# touch_7.net
KiCad netlist of a schematic drawn in EAGLE
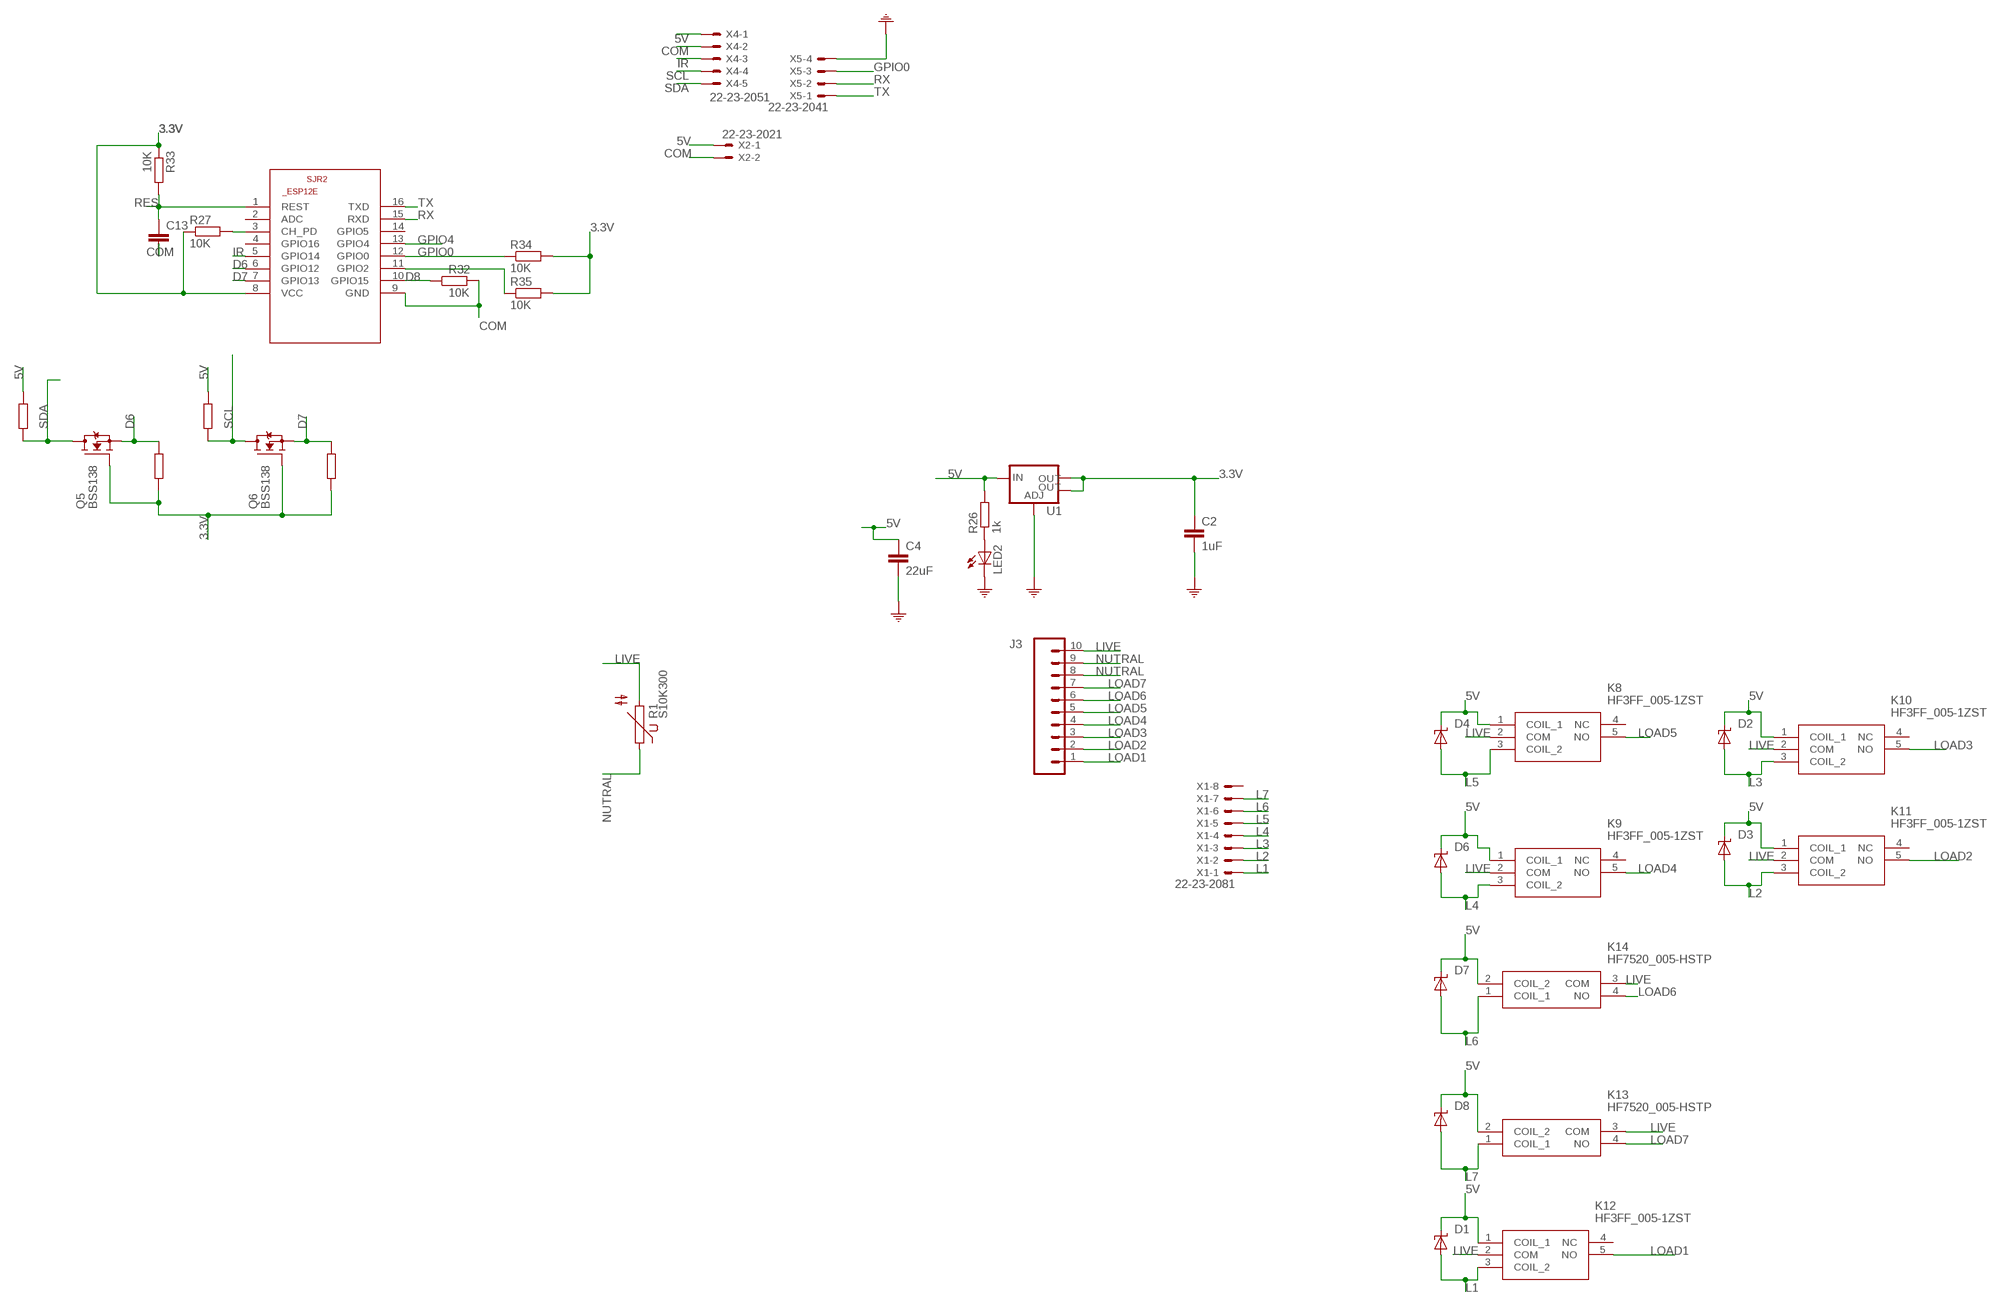
[diagram p0: schematic, sheet 1]

(export (version "E")
  (design (tool "Eeschema 10.0.6"))
  (components
    (comp (ref "C2")
      (value "1uF")
      (footprint "eagle-import:C1206")
      (libsource (lib "eagle-import") (part "C-EUC1206"))
    )
    (comp (ref "C4")
      (value "22uF")
      (footprint "eagle-import:C1206")
      (libsource (lib "eagle-import") (part "C-EUC1206"))
    )
    (comp (ref "C13")
      (value "C-EUC0805")
      (footprint "eagle-import:C0805")
      (libsource (lib "eagle-import") (part "C-EUC0805"))
    )
    (comp (ref "D1")
      (value "SUPPRESSOR-SMBJ")
      (footprint "eagle-import:SMBJ")
      (libsource (lib "eagle-import") (part "SUPPRESSOR-SMBJ"))
    )
    (comp (ref "D2")
      (value "SUPPRESSOR-SMBJ")
      (footprint "eagle-import:SMBJ")
      (libsource (lib "eagle-import") (part "SUPPRESSOR-SMBJ"))
    )
    (comp (ref "D3")
      (value "SUPPRESSOR-SMBJ")
      (footprint "eagle-import:SMBJ")
      (libsource (lib "eagle-import") (part "SUPPRESSOR-SMBJ"))
    )
    (comp (ref "D4")
      (value "SUPPRESSOR-SMBJ")
      (footprint "eagle-import:SMBJ")
      (libsource (lib "eagle-import") (part "SUPPRESSOR-SMBJ"))
    )
    (comp (ref "D6")
      (value "SUPPRESSOR-SMBJ")
      (footprint "eagle-import:SMBJ")
      (libsource (lib "eagle-import") (part "SUPPRESSOR-SMBJ"))
    )
    (comp (ref "D7")
      (value "SUPPRESSOR-SMBJ")
      (footprint "eagle-import:SMBJ")
      (libsource (lib "eagle-import") (part "SUPPRESSOR-SMBJ"))
    )
    (comp (ref "D8")
      (value "SUPPRESSOR-SMBJ")
      (footprint "eagle-import:SMBJ")
      (libsource (lib "eagle-import") (part "SUPPRESSOR-SMBJ"))
    )
    (comp (ref "J3")
      (value "CONN_083.5MM-8")
      (footprint "eagle-import:SCREWTERMINAL-3.5MM-8")
      (libsource (lib "eagle-import") (part "CONN_083.5MM-8"))
    )
    (comp (ref "K8")
      (value "HF3FF_005-1ZST")
      (footprint "eagle-import:HF3FF0051ZST")
      (fields (field (name "ARROW_PART_NUMBER") "HF3FF/005-1ZST"))
      (libsource (lib "eagle-import") (part "HF3FF_005-1ZST"))
    )
    (comp (ref "K9")
      (value "HF3FF_005-1ZST")
      (footprint "eagle-import:HF3FF0051ZST")
      (fields (field (name "ARROW_PART_NUMBER") "HF3FF/005-1ZST"))
      (libsource (lib "eagle-import") (part "HF3FF_005-1ZST"))
    )
    (comp (ref "K10")
      (value "HF3FF_005-1ZST")
      (footprint "eagle-import:HF3FF0051ZST")
      (fields (field (name "ARROW_PART_NUMBER") "HF3FF/005-1ZST"))
      (libsource (lib "eagle-import") (part "HF3FF_005-1ZST"))
    )
    (comp (ref "K11")
      (value "HF3FF_005-1ZST")
      (footprint "eagle-import:HF3FF0051ZST")
      (fields (field (name "ARROW_PART_NUMBER") "HF3FF/005-1ZST"))
      (libsource (lib "eagle-import") (part "HF3FF_005-1ZST"))
    )
    (comp (ref "K12")
      (value "HF3FF_005-1ZST")
      (footprint "eagle-import:HF3FF0051ZST")
      (fields (field (name "ARROW_PART_NUMBER") "HF3FF/005-1ZST"))
      (libsource (lib "eagle-import") (part "HF3FF_005-1ZST"))
    )
    (comp (ref "K13")
      (value "HF7520_005-HSTP")
      (footprint "eagle-import:HF7520005HSTP")
      (fields (field (name "ARROW_PART_NUMBER") "HF7520/005-HSTP"))
      (libsource (lib "eagle-import") (part "HF7520_005-HSTP"))
    )
    (comp (ref "K14")
      (value "HF7520_005-HSTP")
      (footprint "eagle-import:HF7520005HSTP")
      (fields (field (name "ARROW_PART_NUMBER") "HF7520/005-HSTP"))
      (libsource (lib "eagle-import") (part "HF7520_005-HSTP"))
    )
    (comp (ref "LED2")
      (value "LEDCHIPLED_1206")
      (footprint "eagle-import:CHIPLED_1206")
      (libsource (lib "eagle-import") (part "LEDCHIPLED_1206"))
    )
    (comp (ref "Q5")
      (value "BSS138")
      (footprint "eagle-import:SOT23")
      (fields (field (name "MF") "Fairchild"))
      (libsource (lib "eagle-import") (part "BSS138"))
    )
    (comp (ref "Q6")
      (value "BSS138")
      (footprint "eagle-import:SOT23")
      (fields (field (name "MF") "Fairchild"))
      (libsource (lib "eagle-import") (part "BSS138"))
    )
    (comp (ref "R1")
      (value "S10K300")
      (footprint "eagle-import:S10K300")
      (libsource (lib "eagle-import") (part "S10K300"))
    )
    (comp (ref "R26")
      (value "1k")
      (footprint "eagle-import:R0805")
      (libsource (lib "eagle-import") (part "R-EU_R0805"))
    )
    (comp (ref "R27")
      (value "10K")
      (footprint "eagle-import:R0805")
      (libsource (lib "eagle-import") (part "R-EU_R0805"))
    )
    (comp (ref "R32")
      (value "10K")
      (footprint "eagle-import:R0805")
      (libsource (lib "eagle-import") (part "R-EU_R0805"))
    )
    (comp (ref "R33")
      (value "10K")
      (footprint "eagle-import:R0805")
      (libsource (lib "eagle-import") (part "R-EU_R0805"))
    )
    (comp (ref "R34")
      (value "10K")
      (footprint "eagle-import:R0805")
      (libsource (lib "eagle-import") (part "R-EU_R0805"))
    )
    (comp (ref "R35")
      (value "10K")
      (footprint "eagle-import:R0805")
      (libsource (lib "eagle-import") (part "R-EU_R0805"))
    )
    (comp (ref "R36")
      (value "10K")
      (footprint "eagle-import:R0805")
      (libsource (lib "eagle-import") (part "R-EU_R0805"))
    )
    (comp (ref "R37")
      (value "10K")
      (footprint "eagle-import:R0805")
      (libsource (lib "eagle-import") (part "R-EU_R0805"))
    )
    (comp (ref "R38")
      (value "10K")
      (footprint "eagle-import:R0805")
      (libsource (lib "eagle-import") (part "R-EU_R0805"))
    )
    (comp (ref "R39")
      (value "10K")
      (footprint "eagle-import:R0805")
      (libsource (lib "eagle-import") (part "R-EU_R0805"))
    )
    (comp (ref "SJR2")
      (value "ESP8266-12EESP12E")
      (footprint "eagle-import:ESP8266-ESP12E")
      (libsource (lib "eagle-import") (part "ESP8266-12EESP12E"))
    )
    (comp (ref "U1")
      (value "V_REG_LM1117SOT223")
      (footprint "eagle-import:SOT223")
      (libsource (lib "eagle-import") (part "V_REG_LM1117SOT223"))
    )
    (comp (ref "X1")
      (value "22-23-2081")
      (footprint "eagle-import:22-23-2081")
      (libsource (lib "eagle-import") (part "22-23-2081"))
    )
    (comp (ref "X2")
      (value "22-23-2021")
      (footprint "eagle-import:22-23-2021")
      (libsource (lib "eagle-import") (part "22-23-2021"))
    )
    (comp (ref "X4")
      (value "22-23-2051")
      (footprint "eagle-import:22-23-2051")
      (libsource (lib "eagle-import") (part "22-23-2051"))
    )
    (comp (ref "X5")
      (value "22-23-2041")
      (footprint "eagle-import:22-23-2041")
      (libsource (lib "eagle-import") (part "22-23-2041"))
    )
  )
  (nets
    (net (code "1") (name "/3.3V") (class "Default")
      (node (ref "C2") (pin "1") (pinfunction "1_1") (pintype "passive"))
      (node (ref "Q5") (pin "1") (pinfunction "G_1") (pintype "passive"))
      (node (ref "Q6") (pin "1") (pinfunction "G_1") (pintype "passive"))
      (node (ref "R27") (pin "1") (pinfunction "1_1") (pintype "passive"))
      (node (ref "R33") (pin "1") (pinfunction "1_1") (pintype "passive"))
      (node (ref "R34") (pin "2") (pinfunction "2_2") (pintype "passive"))
      (node (ref "R35") (pin "2") (pinfunction "2_2") (pintype "passive"))
      (node (ref "R37") (pin "2") (pinfunction "2_2") (pintype "passive"))
      (node (ref "R39") (pin "2") (pinfunction "2_2") (pintype "passive"))
      (node (ref "SJR2") (pin "8") (pinfunction "VCC_8") (pintype "bidirectional"))
      (node (ref "U1") (pin "2") (pinfunction "OUT_2") (pintype "output"))
      (node (ref "U1") (pin "4") (pinfunction "OUT_4") (pintype "output"))
    )
    (net (code "2") (name "/5V") (class "Default")
      (node (ref "C4") (pin "1") (pinfunction "1_1") (pintype "passive"))
      (node (ref "D1") (pin "C") (pinfunction "C_C") (pintype "passive"))
      (node (ref "D2") (pin "C") (pinfunction "C_C") (pintype "passive"))
      (node (ref "D3") (pin "C") (pinfunction "C_C") (pintype "passive"))
      (node (ref "D4") (pin "C") (pinfunction "C_C") (pintype "passive"))
      (node (ref "D6") (pin "C") (pinfunction "C_C") (pintype "passive"))
      (node (ref "D7") (pin "C") (pinfunction "C_C") (pintype "passive"))
      (node (ref "D8") (pin "C") (pinfunction "C_C") (pintype "passive"))
      (node (ref "K10") (pin "1") (pinfunction "COIL_1_1") (pintype "bidirectional"))
      (node (ref "K11") (pin "1") (pinfunction "COIL_1_1") (pintype "bidirectional"))
      (node (ref "K12") (pin "1") (pinfunction "COIL_1_1") (pintype "bidirectional"))
      (node (ref "K13") (pin "2") (pinfunction "COIL_2_2") (pintype "bidirectional"))
      (node (ref "K14") (pin "2") (pinfunction "COIL_2_2") (pintype "bidirectional"))
      (node (ref "K8") (pin "1") (pinfunction "COIL_1_1") (pintype "bidirectional"))
      (node (ref "K9") (pin "1") (pinfunction "COIL_1_1") (pintype "bidirectional"))
      (node (ref "R26") (pin "2") (pinfunction "2_2") (pintype "passive"))
      (node (ref "R36") (pin "2") (pinfunction "2_2") (pintype "passive"))
      (node (ref "R38") (pin "2") (pinfunction "2_2") (pintype "passive"))
      (node (ref "U1") (pin "3") (pinfunction "IN_3") (pintype "input"))
      (node (ref "X2") (pin "1") (pinfunction "S_1") (pintype "passive"))
      (node (ref "X4") (pin "1") (pinfunction "S_1") (pintype "passive"))
    )
    (net (code "3") (name "/D6") (class "Default")
      (node (ref "Q5") (pin "2") (pinfunction "S_2") (pintype "passive"))
      (node (ref "R37") (pin "1") (pinfunction "1_1") (pintype "passive"))
      (node (ref "SJR2") (pin "6") (pinfunction "GPIO12_6") (pintype "bidirectional"))
    )
    (net (code "4") (name "/D7") (class "Default")
      (node (ref "Q6") (pin "2") (pinfunction "S_2") (pintype "passive"))
      (node (ref "R39") (pin "1") (pinfunction "1_1") (pintype "passive"))
      (node (ref "SJR2") (pin "7") (pinfunction "GPIO13_7") (pintype "bidirectional"))
    )
    (net (code "5") (name "/D8") (class "Default")
      (node (ref "R32") (pin "1") (pinfunction "1_1") (pintype "passive"))
      (node (ref "SJR2") (pin "10") (pinfunction "GPIO15_10") (pintype "bidirectional"))
    )
    (net (code "6") (name "/GPIO0") (class "Default")
      (node (ref "R34") (pin "1") (pinfunction "1_1") (pintype "passive"))
      (node (ref "SJR2") (pin "12") (pinfunction "GPIO0_12") (pintype "bidirectional"))
      (node (ref "X5") (pin "3") (pinfunction "S_3") (pintype "passive"))
    )
    (net (code "7") (name "/GPIO4") (class "Default")
      (node (ref "SJR2") (pin "13") (pinfunction "GPIO4_13") (pintype "bidirectional"))
    )
    (net (code "8") (name "/IR") (class "Default")
      (node (ref "SJR2") (pin "5") (pinfunction "GPIO14_5") (pintype "bidirectional"))
      (node (ref "X4") (pin "3") (pinfunction "S_3") (pintype "passive"))
    )
    (net (code "9") (name "/L1") (class "Default")
      (node (ref "D1") (pin "A") (pinfunction "A_A") (pintype "passive"))
      (node (ref "K12") (pin "3") (pinfunction "COIL_2_3") (pintype "bidirectional"))
      (node (ref "X1") (pin "1") (pinfunction "S_1") (pintype "passive"))
    )
    (net (code "10") (name "/L2") (class "Default")
      (node (ref "D3") (pin "A") (pinfunction "A_A") (pintype "passive"))
      (node (ref "K11") (pin "3") (pinfunction "COIL_2_3") (pintype "bidirectional"))
      (node (ref "X1") (pin "2") (pinfunction "S_2") (pintype "passive"))
    )
    (net (code "11") (name "/L3") (class "Default")
      (node (ref "D2") (pin "A") (pinfunction "A_A") (pintype "passive"))
      (node (ref "K10") (pin "3") (pinfunction "COIL_2_3") (pintype "bidirectional"))
      (node (ref "X1") (pin "3") (pinfunction "S_3") (pintype "passive"))
    )
    (net (code "12") (name "/L4") (class "Default")
      (node (ref "D6") (pin "A") (pinfunction "A_A") (pintype "passive"))
      (node (ref "K9") (pin "3") (pinfunction "COIL_2_3") (pintype "bidirectional"))
      (node (ref "X1") (pin "4") (pinfunction "S_4") (pintype "passive"))
    )
    (net (code "13") (name "/L5") (class "Default")
      (node (ref "D4") (pin "A") (pinfunction "A_A") (pintype "passive"))
      (node (ref "K8") (pin "3") (pinfunction "COIL_2_3") (pintype "bidirectional"))
      (node (ref "X1") (pin "5") (pinfunction "S_5") (pintype "passive"))
    )
    (net (code "14") (name "/L6") (class "Default")
      (node (ref "D7") (pin "A") (pinfunction "A_A") (pintype "passive"))
      (node (ref "K14") (pin "1") (pinfunction "COIL_1_1") (pintype "bidirectional"))
      (node (ref "X1") (pin "6") (pinfunction "S_6") (pintype "passive"))
    )
    (net (code "15") (name "/L7") (class "Default")
      (node (ref "D8") (pin "A") (pinfunction "A_A") (pintype "passive"))
      (node (ref "K13") (pin "1") (pinfunction "COIL_1_1") (pintype "bidirectional"))
      (node (ref "X1") (pin "7") (pinfunction "S_7") (pintype "passive"))
    )
    (net (code "16") (name "/LIVE") (class "Default")
      (node (ref "J3") (pin "10") (pinfunction "10_10") (pintype "passive"))
      (node (ref "K10") (pin "2") (pinfunction "COM_2") (pintype "bidirectional"))
      (node (ref "K11") (pin "2") (pinfunction "COM_2") (pintype "bidirectional"))
      (node (ref "K12") (pin "2") (pinfunction "COM_2") (pintype "bidirectional"))
      (node (ref "K13") (pin "3") (pinfunction "COM_3") (pintype "bidirectional"))
      (node (ref "K14") (pin "3") (pinfunction "COM_3") (pintype "bidirectional"))
      (node (ref "K8") (pin "2") (pinfunction "COM_2") (pintype "bidirectional"))
      (node (ref "K9") (pin "2") (pinfunction "COM_2") (pintype "bidirectional"))
      (node (ref "R1") (pin "2") (pinfunction "2_2") (pintype "passive"))
    )
    (net (code "17") (name "/LOAD1") (class "Default")
      (node (ref "J3") (pin "1") (pinfunction "1_1") (pintype "passive"))
      (node (ref "K12") (pin "5") (pinfunction "NO_5") (pintype "bidirectional"))
    )
    (net (code "18") (name "/LOAD2") (class "Default")
      (node (ref "J3") (pin "2") (pinfunction "2_2") (pintype "passive"))
      (node (ref "K11") (pin "5") (pinfunction "NO_5") (pintype "bidirectional"))
    )
    (net (code "19") (name "/LOAD3") (class "Default")
      (node (ref "J3") (pin "3") (pinfunction "3_3") (pintype "passive"))
      (node (ref "K10") (pin "5") (pinfunction "NO_5") (pintype "bidirectional"))
    )
    (net (code "20") (name "/LOAD4") (class "Default")
      (node (ref "J3") (pin "4") (pinfunction "4_4") (pintype "passive"))
      (node (ref "K9") (pin "5") (pinfunction "NO_5") (pintype "bidirectional"))
    )
    (net (code "21") (name "/LOAD5") (class "Default")
      (node (ref "J3") (pin "5") (pinfunction "5_5") (pintype "passive"))
      (node (ref "K8") (pin "5") (pinfunction "NO_5") (pintype "bidirectional"))
    )
    (net (code "22") (name "/LOAD6") (class "Default")
      (node (ref "J3") (pin "6") (pinfunction "6_6") (pintype "passive"))
      (node (ref "K14") (pin "4") (pinfunction "NO_4") (pintype "bidirectional"))
    )
    (net (code "23") (name "/LOAD7") (class "Default")
      (node (ref "J3") (pin "7") (pinfunction "7_7") (pintype "passive"))
      (node (ref "K13") (pin "4") (pinfunction "NO_4") (pintype "bidirectional"))
    )
    (net (code "24") (name "/NUTRAL") (class "Default")
      (node (ref "J3") (pin "8") (pinfunction "8_8") (pintype "passive"))
      (node (ref "J3") (pin "9") (pinfunction "9_9") (pintype "passive"))
      (node (ref "R1") (pin "1") (pinfunction "1_1") (pintype "passive"))
    )
    (net (code "25") (name "/RES") (class "Default")
      (node (ref "C13") (pin "1") (pinfunction "1_1") (pintype "passive"))
      (node (ref "R33") (pin "2") (pinfunction "2_2") (pintype "passive"))
      (node (ref "SJR2") (pin "1") (pinfunction "REST_1") (pintype "bidirectional"))
    )
    (net (code "26") (name "/RX") (class "Default")
      (node (ref "SJR2") (pin "15") (pinfunction "RXD_15") (pintype "bidirectional"))
      (node (ref "X5") (pin "2") (pinfunction "S_2") (pintype "passive"))
    )
    (net (code "27") (name "/SCL") (class "Default")
      (node (ref "Q6") (pin "3") (pinfunction "D_3") (pintype "passive"))
      (node (ref "R36") (pin "1") (pinfunction "1_1") (pintype "passive"))
      (node (ref "X4") (pin "4") (pinfunction "S_4") (pintype "passive"))
    )
    (net (code "28") (name "/SDA") (class "Default")
      (node (ref "Q5") (pin "3") (pinfunction "D_3") (pintype "passive"))
      (node (ref "R38") (pin "1") (pinfunction "1_1") (pintype "passive"))
      (node (ref "X4") (pin "5") (pinfunction "S_5") (pintype "passive"))
    )
    (net (code "29") (name "/TX") (class "Default")
      (node (ref "SJR2") (pin "16") (pinfunction "TXD_16") (pintype "bidirectional"))
      (node (ref "X5") (pin "1") (pinfunction "S_1") (pintype "passive"))
    )
    (net (code "30") (name "COM") (class "Default")
      (node (ref "C13") (pin "2") (pinfunction "2_2") (pintype "passive"))
      (node (ref "C2") (pin "2") (pinfunction "2_2") (pintype "passive"))
      (node (ref "C4") (pin "2") (pinfunction "2_2") (pintype "passive"))
      (node (ref "LED2") (pin "C") (pinfunction "C_C") (pintype "passive"))
      (node (ref "R32") (pin "2") (pinfunction "2_2") (pintype "passive"))
      (node (ref "SJR2") (pin "9") (pinfunction "GND_9") (pintype "bidirectional"))
      (node (ref "U1") (pin "1") (pinfunction "ADJ_1") (pintype "input"))
      (node (ref "X2") (pin "2") (pinfunction "S_2") (pintype "passive"))
      (node (ref "X4") (pin "2") (pinfunction "S_2") (pintype "passive"))
      (node (ref "X5") (pin "4") (pinfunction "S_4") (pintype "passive"))
    )
    (net (code "31") (name "Net-(LED2-PadA)") (class "Default")
      (node (ref "LED2") (pin "A") (pinfunction "A_A") (pintype "passive"))
      (node (ref "R26") (pin "1") (pinfunction "1_1") (pintype "passive"))
    )
    (net (code "32") (name "Net-(SJR2-CH_PD)") (class "Default")
      (node (ref "R27") (pin "2") (pinfunction "2_2") (pintype "passive"))
      (node (ref "SJR2") (pin "3") (pinfunction "CH_PD_3") (pintype "bidirectional"))
    )
    (net (code "33") (name "Net-(SJR2-GPIO2)") (class "Default")
      (node (ref "R35") (pin "1") (pinfunction "1_1") (pintype "passive"))
      (node (ref "SJR2") (pin "11") (pinfunction "GPIO2_11") (pintype "bidirectional"))
    )
    (net (code "34") (name "unconnected-(K8-NC-Pad4)") (class "Default")
      (node (ref "K8") (pin "4") (pinfunction "NC_4") (pintype "no_connect"))
    )
    (net (code "35") (name "unconnected-(K9-NC-Pad4)") (class "Default")
      (node (ref "K9") (pin "4") (pinfunction "NC_4") (pintype "no_connect"))
    )
    (net (code "36") (name "unconnected-(K10-NC-Pad4)") (class "Default")
      (node (ref "K10") (pin "4") (pinfunction "NC_4") (pintype "no_connect"))
    )
    (net (code "37") (name "unconnected-(K11-NC-Pad4)") (class "Default")
      (node (ref "K11") (pin "4") (pinfunction "NC_4") (pintype "no_connect"))
    )
    (net (code "38") (name "unconnected-(K12-NC-Pad4)") (class "Default")
      (node (ref "K12") (pin "4") (pinfunction "NC_4") (pintype "no_connect"))
    )
    (net (code "39") (name "unconnected-(SJR2-ADC-Pad2)") (class "Default")
      (node (ref "SJR2") (pin "2") (pinfunction "ADC_2") (pintype "bidirectional"))
    )
    (net (code "40") (name "unconnected-(SJR2-GPIO5-Pad14)") (class "Default")
      (node (ref "SJR2") (pin "14") (pinfunction "GPIO5_14") (pintype "bidirectional"))
    )
    (net (code "41") (name "unconnected-(SJR2-GPIO16-Pad4)") (class "Default")
      (node (ref "SJR2") (pin "4") (pinfunction "GPIO16_4") (pintype "bidirectional"))
    )
    (net (code "42") (name "unconnected-(X1H-S-Pad8)") (class "Default")
      (node (ref "X1") (pin "8") (pinfunction "S_8") (pintype "passive"))
    )
  )
)
